# SolarPanelZPlus.net
KiCad netlist of a schematic drawn in Altium Designer
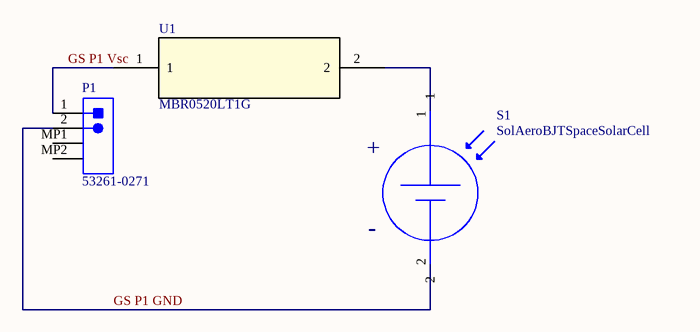
[diagram p0: SolarPanelZPlus.SchDoc]

(export (version "E")
  (design (tool "Eeschema 10.0.6"))
  (components
    (comp (ref "P1")
      (value "53261-0271")
      (footprint "MOLX-53261-0271_V")
      (description "PicoBlade(TM) Header, Right Angle, -40 to 85 degC, 2-Pin SMD, RoHS, Tape and Reel")
      (fields (field (name "MANUFACTURER") "Molex"))
      (libsource (lib "Altium Content Vault") (part "CMP-2000-05633-1"))
    )
    (comp (ref "S1")
      (value "SolAeroBJTSpaceSolarCell")
      (libsource (lib "SolarPanelZPlus") (part "SolAeroBJTSpaceSolarCell"))
    )
    (comp (ref "U1")
      (value "MBR0520LT1G")
      (footprint "SOD-123")
      (description "Imported")
      (fields (field (name "COPYRIGHT") "Copyright (C) 2015 Accelerated Designs. All rights reserved"))
      (libsource (lib "MBR0520LT1G") (part "MBR0520LT1G"))
    )
  )
  (nets
    (net (code "1") (name "/GS P1 GND") (class "Default")
      (node (ref "P1") (pin "2") (pinfunction "2_2") (pintype "passive"))
      (node (ref "S1") (pin "2") (pinfunction "2_2") (pintype "passive"))
    )
    (net (code "2") (name "/GS P1 Vsc") (class "Default")
      (node (ref "P1") (pin "1") (pinfunction "1_1") (pintype "passive"))
      (node (ref "U1") (pin "1") (pinfunction "1_1") (pintype "passive"))
    )
    (net (code "3") (name "Net-(S1-Pad1)") (class "Default")
      (node (ref "S1") (pin "1") (pinfunction "1_1") (pintype "power_in"))
      (node (ref "U1") (pin "2") (pinfunction "2_2") (pintype "passive"))
    )
    (net (code "4") (name "unconnected-(P1-PadMP1)") (class "Default")
      (node (ref "P1") (pin "MP1") (pinfunction "MP1_MP1") (pintype "passive"))
    )
    (net (code "5") (name "unconnected-(P1-PadMP2)") (class "Default")
      (node (ref "P1") (pin "MP2") (pinfunction "MP2_MP2") (pintype "passive"))
    )
  )
)
